# Voltage_Measurement.net
KiCad netlist of a schematic drawn in Altium Designer
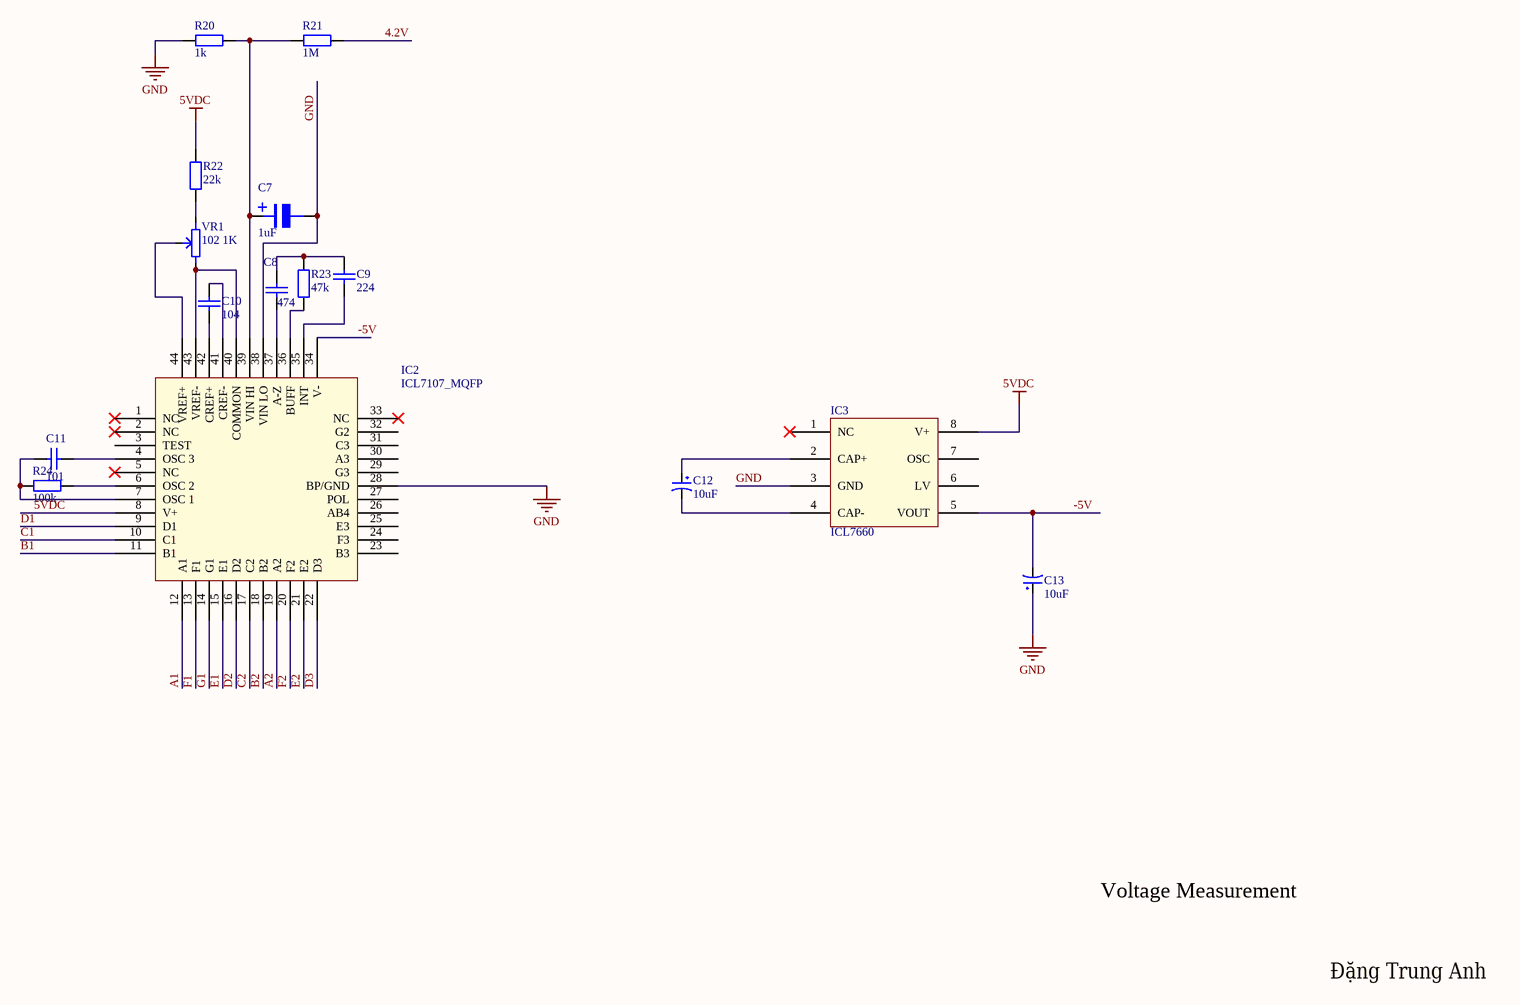
[diagram p0: Voltage Measurement.SchDoc]

(export (version "E")
  (design (tool "Eeschema 10.0.6"))
  (components
    (comp (ref "C7")
      (value "1uF")
      (footprint "tu nhom 4 (B)")
      (description "Dán")
      (libsource (lib "Altium_Lib_by_KhueNguyenCreator") (part "Tu Nhom 1uF 50V"))
    )
    (comp (ref "C8")
      (value "474")
      (footprint "tu 0805")
      (description "Dán")
      (libsource (lib "Altium_Lib_by_KhueNguyenCreator") (part "Tu 0805 474 50V 10%"))
    )
    (comp (ref "C9")
      (value "224")
      (footprint "tu 0805")
      (description "Dán")
      (libsource (lib "Altium_Lib_by_KhueNguyenCreator") (part "Tu 0805 224 50V 10%"))
    )
    (comp (ref "C10")
      (value "104")
      (footprint "tu 0805")
      (description "Dán")
      (libsource (lib "THU VIEN SCH") (part "Tu 0805 104 50V 10%"))
    )
    (comp (ref "C11")
      (value "101")
      (footprint "tu 0805")
      (description "Dán")
      (libsource (lib "Altium_Lib_by_KhueNguyenCreator") (part "Tu 0805 101 50V 20%"))
    )
    (comp (ref "C12")
      (value "10uF")
      (footprint "tu hoa 4mm")
      (description "Cắm")
      (libsource (lib "THU VIEN SCH") (part "Tu Hoa 10uF 25V 4x7"))
    )
    (comp (ref "C13")
      (value "10uF")
      (footprint "tu hoa 4mm")
      (description "Cắm")
      (libsource (lib "THU VIEN SCH") (part "Tu Hoa 10uF 25V 4x7"))
    )
    (comp (ref "IC2")
      (value "ICL7107_MQFP")
      (footprint "ICL7107_MQFP44")
      (libsource (lib "Integrated_Library") (part "ICL7107_MQFP"))
    )
    (comp (ref "IC3")
      (value "ICL7660")
      (footprint "SOIC8_ICL7660")
      (libsource (lib "Integrated_Library") (part "ICL7660_SOIC8"))
    )
    (comp (ref "R20")
      (value "1k")
      (footprint "tro smd 0805")
      (description "Dán")
      (libsource (lib "THU VIEN SCH") (part "Tro 0805 5% 1k"))
    )
    (comp (ref "R21")
      (value "1M")
      (footprint "tro smd 0805")
      (description "Dán")
      (libsource (lib "THU VIEN SCH") (part "Tro 0805 5% 1M"))
    )
    (comp (ref "R22")
      (value "22k")
      (footprint "tro smd 0805")
      (description "Dán")
      (libsource (lib "THU VIEN SCH") (part "Tro 0805 5% 22k"))
    )
    (comp (ref "R23")
      (value "47k")
      (footprint "tro smd 0805")
      (description "Dán")
      (libsource (lib "Altium_Lib_by_KhueNguyenCreator") (part "Tro 0805 5% 47k"))
    )
    (comp (ref "R24")
      (value "100k")
      (footprint "tro smd 0805")
      (description "Dán")
      (libsource (lib "THU VIEN SCH") (part "Tro 0805 5% 100k"))
    )
    (comp (ref "VR1")
      (value "102 1K")
      (footprint "VR Tam Giac")
      (description "Cắm")
      (libsource (lib "THU VIEN SCH") (part "Bien tro tam giac 1K"))
    )
  )
  (nets
    (net (code "1") (name "/-5V") (class "Default")
      (node (ref "C13") (pin "2") (pinfunction "2_2") (pintype "passive"))
      (node (ref "IC2") (pin "34") (pinfunction "V-_34") (pintype "passive"))
      (node (ref "IC3") (pin "5") (pinfunction "VOUT_5") (pintype "passive"))
    )
    (net (code "2") (name "/4.2V") (class "Default")
      (node (ref "R21") (pin "1") (pinfunction "1_1") (pintype "passive"))
    )
    (net (code "3") (name "/A1") (class "Default")
      (node (ref "IC2") (pin "12") (pinfunction "A1_12") (pintype "passive"))
    )
    (net (code "4") (name "/A2") (class "Default")
      (node (ref "IC2") (pin "19") (pinfunction "A2_19") (pintype "passive"))
    )
    (net (code "5") (name "/B1") (class "Default")
      (node (ref "IC2") (pin "11") (pinfunction "B1_11") (pintype "passive"))
    )
    (net (code "6") (name "/B2") (class "Default")
      (node (ref "IC2") (pin "18") (pinfunction "B2_18") (pintype "passive"))
    )
    (net (code "7") (name "/C1") (class "Default")
      (node (ref "IC2") (pin "10") (pinfunction "C1_10") (pintype "passive"))
    )
    (net (code "8") (name "/C2") (class "Default")
      (node (ref "IC2") (pin "17") (pinfunction "C2_17") (pintype "passive"))
    )
    (net (code "9") (name "/D1") (class "Default")
      (node (ref "IC2") (pin "9") (pinfunction "D1_9") (pintype "passive"))
    )
    (net (code "10") (name "/D2") (class "Default")
      (node (ref "IC2") (pin "16") (pinfunction "D2_16") (pintype "passive"))
    )
    (net (code "11") (name "/D3") (class "Default")
      (node (ref "IC2") (pin "22") (pinfunction "D3_22") (pintype "passive"))
    )
    (net (code "12") (name "/E1") (class "Default")
      (node (ref "IC2") (pin "15") (pinfunction "E1_15") (pintype "passive"))
    )
    (net (code "13") (name "/E2") (class "Default")
      (node (ref "IC2") (pin "21") (pinfunction "E2_21") (pintype "passive"))
    )
    (net (code "14") (name "/F1") (class "Default")
      (node (ref "IC2") (pin "13") (pinfunction "F1_13") (pintype "passive"))
    )
    (net (code "15") (name "/F2") (class "Default")
      (node (ref "IC2") (pin "20") (pinfunction "F2_20") (pintype "passive"))
    )
    (net (code "16") (name "/G1") (class "Default")
      (node (ref "IC2") (pin "14") (pinfunction "G1_14") (pintype "passive"))
    )
    (net (code "17") (name "5VDC") (class "Default")
      (node (ref "IC2") (pin "8") (pinfunction "V+_8") (pintype "passive"))
      (node (ref "IC3") (pin "8") (pinfunction "V+_8") (pintype "passive"))
      (node (ref "R22") (pin "2") (pinfunction "2_2") (pintype "passive"))
    )
    (net (code "18") (name "GND") (class "Default")
      (node (ref "C13") (pin "1") (pinfunction "1_1") (pintype "passive"))
      (node (ref "C7") (pin "2") (pinfunction "2_2") (pintype "passive"))
      (node (ref "IC2") (pin "28") (pinfunction "BP/GND_28") (pintype "passive"))
      (node (ref "IC2") (pin "38") (pinfunction "VIN_LO_38") (pintype "passive"))
      (node (ref "IC3") (pin "3") (pinfunction "GND_3") (pintype "passive"))
      (node (ref "R20") (pin "2") (pinfunction "2_2") (pintype "passive"))
    )
    (net (code "19") (name "Net-(C8-Pad1)") (class "Default")
      (node (ref "C8") (pin "1") (pinfunction "1_1") (pintype "passive"))
      (node (ref "C9") (pin "1") (pinfunction "1_1") (pintype "passive"))
      (node (ref "R23") (pin "2") (pinfunction "2_2") (pintype "passive"))
    )
    (net (code "20") (name "Net-(IC2-A-Z)") (class "Default")
      (node (ref "C8") (pin "2") (pinfunction "2_2") (pintype "passive"))
      (node (ref "IC2") (pin "37") (pinfunction "A-Z_37") (pintype "passive"))
    )
    (net (code "21") (name "Net-(IC2-BUFF)") (class "Default")
      (node (ref "IC2") (pin "36") (pinfunction "BUFF_36") (pintype "passive"))
      (node (ref "R23") (pin "1") (pinfunction "1_1") (pintype "passive"))
    )
    (net (code "22") (name "Net-(IC2-COMMON)") (class "Default")
      (node (ref "IC2") (pin "40") (pinfunction "COMMON_40") (pintype "passive"))
      (node (ref "IC2") (pin "43") (pinfunction "VREF-_43") (pintype "passive"))
      (node (ref "VR1") (pin "1") (pinfunction "1_1") (pintype "passive"))
    )
    (net (code "23") (name "Net-(IC2-CREF+)") (class "Default")
      (node (ref "C10") (pin "1") (pinfunction "1_1") (pintype "passive"))
      (node (ref "IC2") (pin "42") (pinfunction "CREF+_42") (pintype "passive"))
    )
    (net (code "24") (name "Net-(IC2-CREF-)") (class "Default")
      (node (ref "C10") (pin "2") (pinfunction "2_2") (pintype "passive"))
      (node (ref "IC2") (pin "41") (pinfunction "CREF-_41") (pintype "passive"))
    )
    (net (code "25") (name "Net-(IC2-INT)") (class "Default")
      (node (ref "C9") (pin "2") (pinfunction "2_2") (pintype "passive"))
      (node (ref "IC2") (pin "35") (pinfunction "INT_35") (pintype "passive"))
    )
    (net (code "26") (name "Net-(IC2-OSC_1)") (class "Default")
      (node (ref "C11") (pin "2") (pinfunction "2_2") (pintype "passive"))
      (node (ref "IC2") (pin "7") (pinfunction "OSC_1_7") (pintype "passive"))
      (node (ref "R24") (pin "1") (pinfunction "1_1") (pintype "passive"))
    )
    (net (code "27") (name "Net-(IC2-OSC_2)") (class "Default")
      (node (ref "IC2") (pin "6") (pinfunction "OSC_2_6") (pintype "passive"))
      (node (ref "R24") (pin "2") (pinfunction "2_2") (pintype "passive"))
    )
    (net (code "28") (name "Net-(IC2-OSC_3)") (class "Default")
      (node (ref "C11") (pin "1") (pinfunction "1_1") (pintype "passive"))
      (node (ref "IC2") (pin "4") (pinfunction "OSC_3_4") (pintype "passive"))
    )
    (net (code "29") (name "Net-(IC2-VIN_HI)") (class "Default")
      (node (ref "C7") (pin "1") (pinfunction "1_1") (pintype "passive"))
      (node (ref "IC2") (pin "39") (pinfunction "VIN_HI_39") (pintype "passive"))
      (node (ref "R20") (pin "1") (pinfunction "1_1") (pintype "passive"))
      (node (ref "R21") (pin "2") (pinfunction "2_2") (pintype "passive"))
    )
    (net (code "30") (name "Net-(IC2-VREF+)") (class "Default")
      (node (ref "IC2") (pin "44") (pinfunction "VREF+_44") (pintype "passive"))
      (node (ref "VR1") (pin "2") (pinfunction "2_2") (pintype "passive"))
    )
    (net (code "31") (name "Net-(IC3-CAP+)") (class "Default")
      (node (ref "C12") (pin "1") (pinfunction "1_1") (pintype "passive"))
      (node (ref "IC3") (pin "2") (pinfunction "CAP+_2") (pintype "passive"))
    )
    (net (code "32") (name "Net-(IC3-CAP-)") (class "Default")
      (node (ref "C12") (pin "2") (pinfunction "2_2") (pintype "passive"))
      (node (ref "IC3") (pin "4") (pinfunction "CAP-_4") (pintype "passive"))
    )
    (net (code "33") (name "Net-(R22-Pad1)") (class "Default")
      (node (ref "R22") (pin "1") (pinfunction "1_1") (pintype "passive"))
      (node (ref "VR1") (pin "3") (pinfunction "3_3") (pintype "passive"))
    )
    (net (code "34") (name "unconnected-(IC2-A3-Pad30)") (class "Default")
      (node (ref "IC2") (pin "30") (pinfunction "A3_30") (pintype "passive"))
    )
    (net (code "35") (name "unconnected-(IC2-AB4-Pad26)") (class "Default")
      (node (ref "IC2") (pin "26") (pinfunction "AB4_26") (pintype "passive"))
    )
    (net (code "36") (name "unconnected-(IC2-B3-Pad23)") (class "Default")
      (node (ref "IC2") (pin "23") (pinfunction "B3_23") (pintype "passive"))
    )
    (net (code "37") (name "unconnected-(IC2-C3-Pad31)") (class "Default")
      (node (ref "IC2") (pin "31") (pinfunction "C3_31") (pintype "passive"))
    )
    (net (code "38") (name "unconnected-(IC2-E3-Pad25)") (class "Default")
      (node (ref "IC2") (pin "25") (pinfunction "E3_25") (pintype "passive"))
    )
    (net (code "39") (name "unconnected-(IC2-F3-Pad24)") (class "Default")
      (node (ref "IC2") (pin "24") (pinfunction "F3_24") (pintype "passive"))
    )
    (net (code "40") (name "unconnected-(IC2-G2-Pad32)") (class "Default")
      (node (ref "IC2") (pin "32") (pinfunction "G2_32") (pintype "passive"))
    )
    (net (code "41") (name "unconnected-(IC2-G3-Pad29)") (class "Default")
      (node (ref "IC2") (pin "29") (pinfunction "G3_29") (pintype "passive"))
    )
    (net (code "42") (name "unconnected-(IC2-NC-Pad1)") (class "Default")
      (node (ref "IC2") (pin "1") (pinfunction "NC_1") (pintype "passive+no_connect"))
    )
    (net (code "43") (name "unconnected-(IC2-NC-Pad2)") (class "Default")
      (node (ref "IC2") (pin "2") (pinfunction "NC_2") (pintype "passive+no_connect"))
    )
    (net (code "44") (name "unconnected-(IC2-NC-Pad5)") (class "Default")
      (node (ref "IC2") (pin "5") (pinfunction "NC_5") (pintype "passive+no_connect"))
    )
    (net (code "45") (name "unconnected-(IC2-NC-Pad33)") (class "Default")
      (node (ref "IC2") (pin "33") (pinfunction "NC_33") (pintype "passive+no_connect"))
    )
    (net (code "46") (name "unconnected-(IC2-POL-Pad27)") (class "Default")
      (node (ref "IC2") (pin "27") (pinfunction "POL_27") (pintype "passive"))
    )
    (net (code "47") (name "unconnected-(IC2-TEST-Pad3)") (class "Default")
      (node (ref "IC2") (pin "3") (pinfunction "TEST_3") (pintype "passive"))
    )
    (net (code "48") (name "unconnected-(IC3-LV-Pad6)") (class "Default")
      (node (ref "IC3") (pin "6") (pinfunction "LV_6") (pintype "passive"))
    )
    (net (code "49") (name "unconnected-(IC3-NC-Pad1)") (class "Default")
      (node (ref "IC3") (pin "1") (pinfunction "NC_1") (pintype "passive+no_connect"))
    )
    (net (code "50") (name "unconnected-(IC3-OSC-Pad7)") (class "Default")
      (node (ref "IC3") (pin "7") (pinfunction "OSC_7") (pintype "passive"))
    )
  )
)
